# wakeup.net
KiCad netlist of a schematic drawn in EAGLE
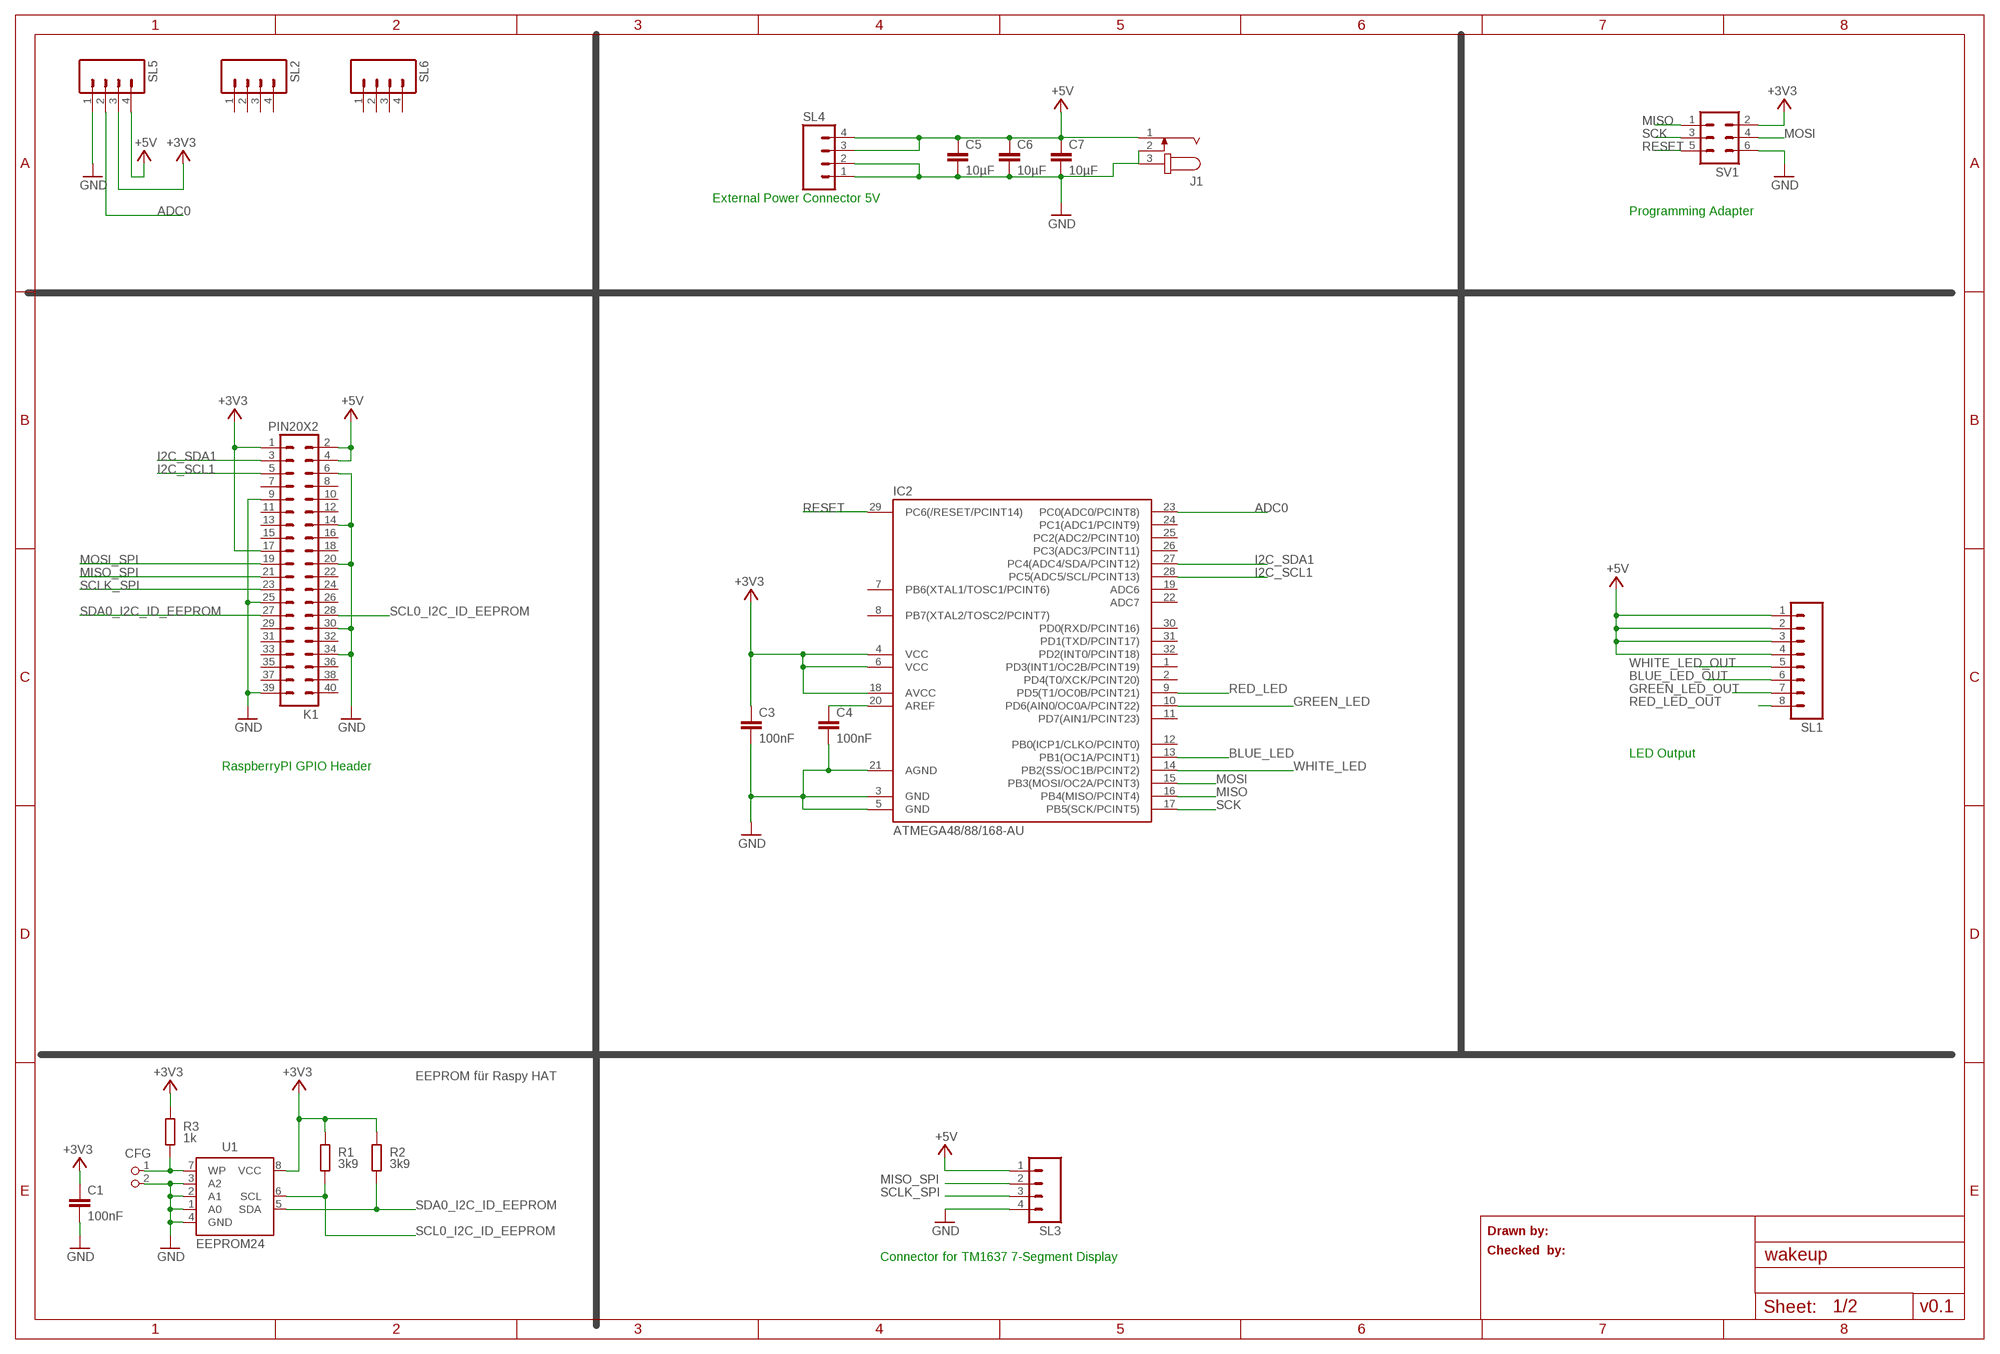
[diagram p0: schematic, sheet 1]
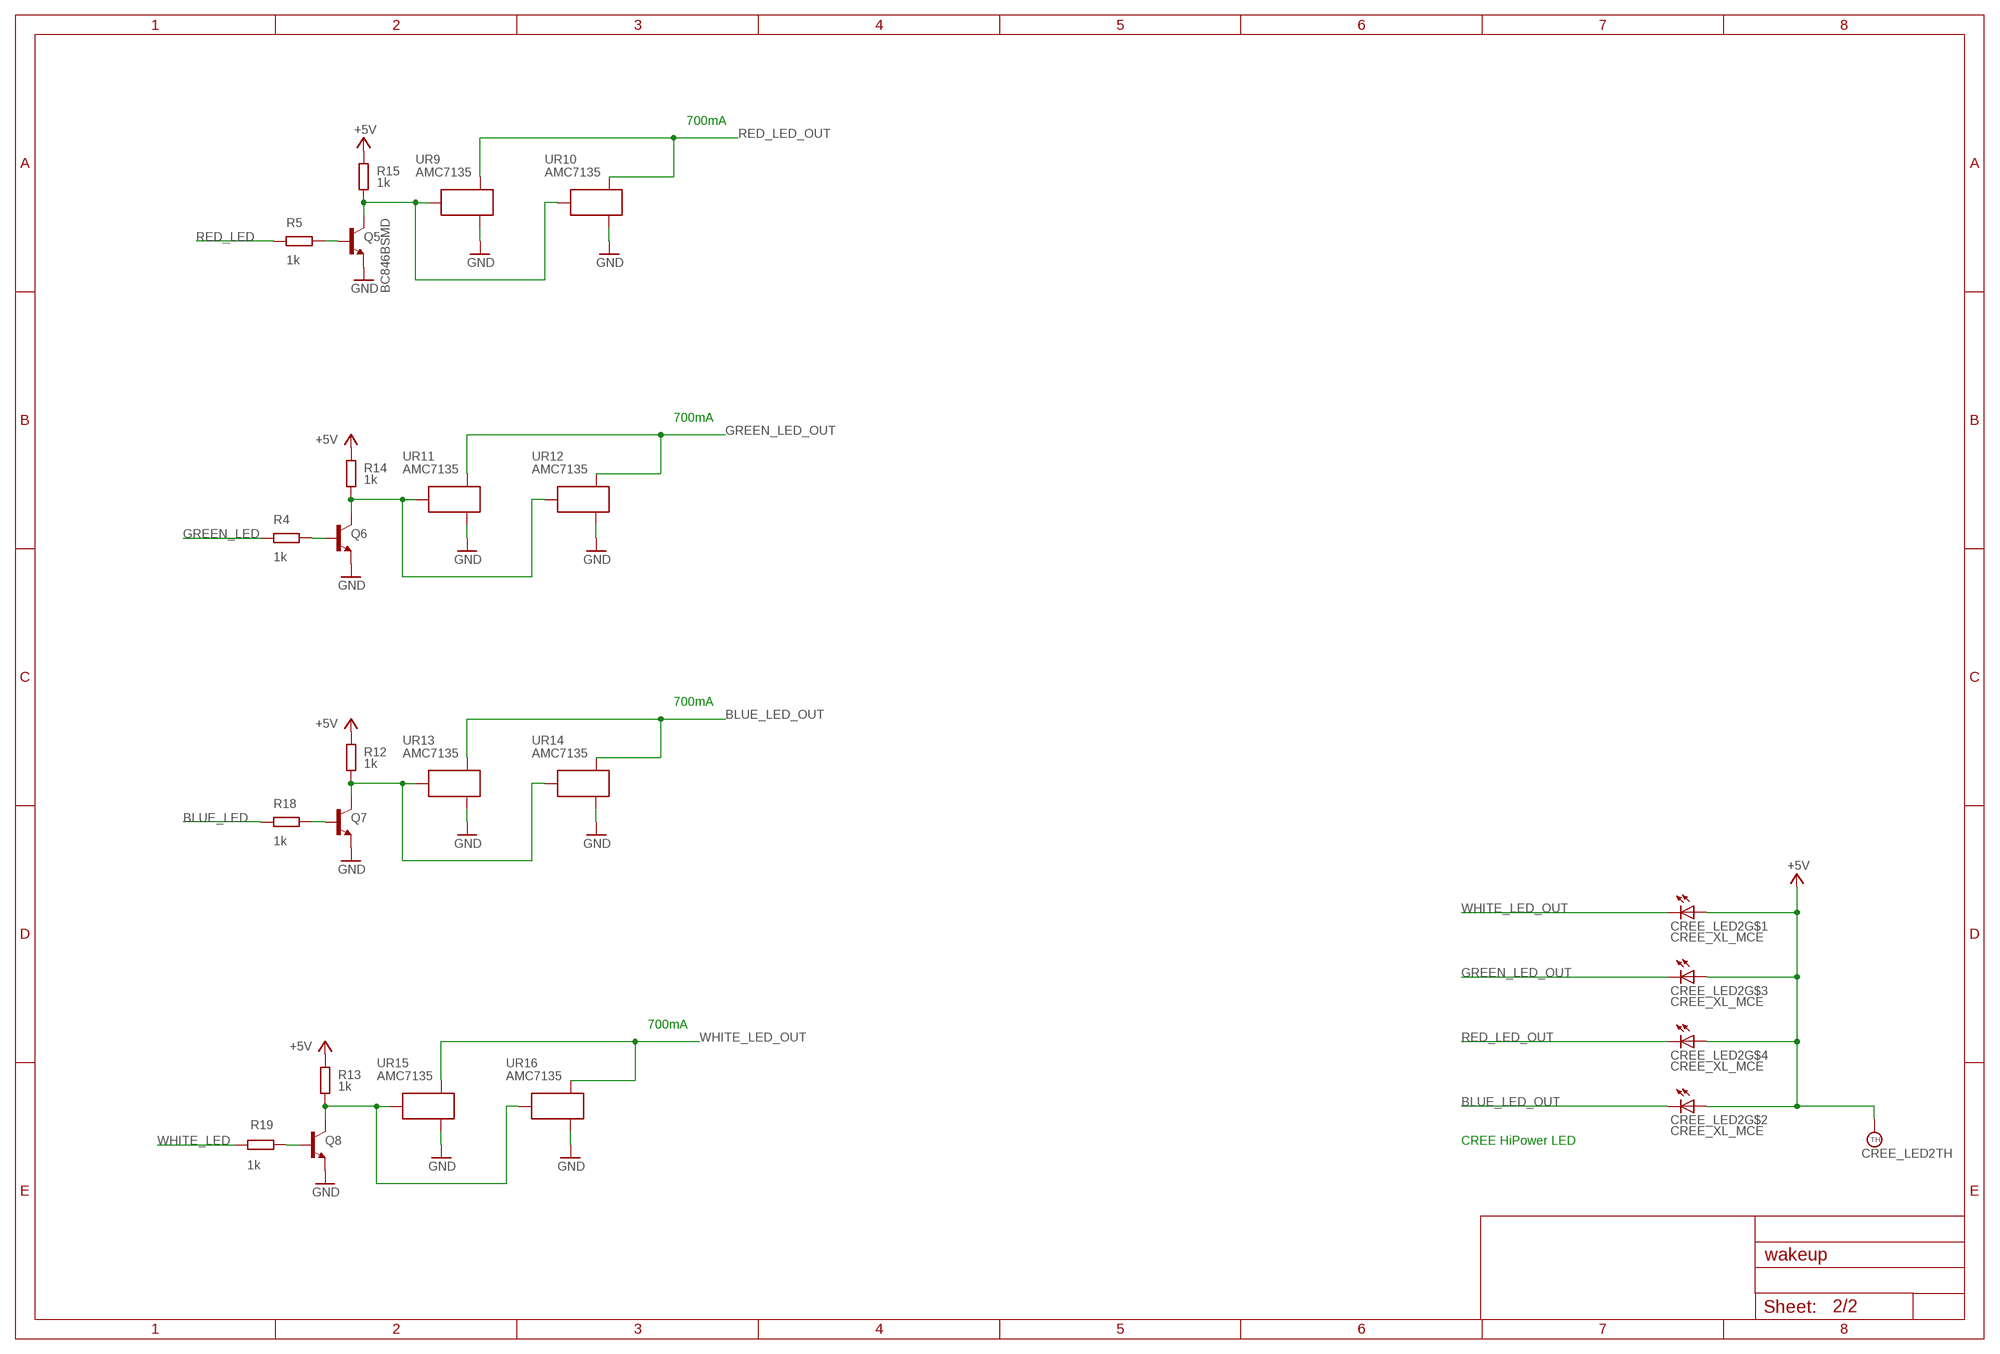
[diagram p1: schematic, sheet 2]

(export (version "E")
  (design (tool "Eeschema 10.0.6"))
  (components
    (comp (ref "C1")
      (value "100nF")
      (footprint "eagle-import:C0805K")
      (libsource (lib "eagle-import") (part "resistor_C-EUC0805K"))
    )
    (comp (ref "C3")
      (value "100nF")
      (footprint "eagle-import:C0603")
      (libsource (lib "eagle-import") (part "C-EUC0603"))
    )
    (comp (ref "C4")
      (value "100nF")
      (footprint "eagle-import:C0603")
      (libsource (lib "eagle-import") (part "C-EUC0603"))
    )
    (comp (ref "C5")
      (value "10µF")
      (footprint "eagle-import:C0805")
      (libsource (lib "eagle-import") (part "C-EUC0805"))
    )
    (comp (ref "C6")
      (value "10µF")
      (footprint "eagle-import:C0805")
      (libsource (lib "eagle-import") (part "C-EUC0805"))
    )
    (comp (ref "C7")
      (value "10µF")
      (footprint "eagle-import:C0805")
      (libsource (lib "eagle-import") (part "C-EUC0805"))
    )
    (comp (ref "CFG")
      (value "PIN2_100")
      (footprint "eagle-import:PIN_W_2")
      (libsource (lib "eagle-import") (part "PIN2_100"))
    )
    (comp (ref "IC2")
      (value "ATMEGA48/88/168-AU")
      (footprint "eagle-import:TQFP32-08")
      (libsource (lib "eagle-import") (part "ATMEGA48/88/168-AU"))
    )
    (comp (ref "J1")
      (value "JACK-PLUG1")
      (footprint "eagle-import:SPC4078")
      (libsource (lib "eagle-import") (part "JACK-PLUG1"))
    )
    (comp (ref "K1")
      (value "PIN20X2")
      (footprint "eagle-import:PIN_20X2")
      (libsource (lib "eagle-import") (part "PIN20X2"))
    )
    (comp (ref "R1")
      (value "3k9")
      (footprint "eagle-import:M0805")
      (fields (field (name "TOLERANCE") "5%"))
      (libsource (lib "eagle-import") (part "R-EU_M0805"))
    )
    (comp (ref "R2")
      (value "3k9")
      (footprint "eagle-import:M0805")
      (fields (field (name "TOLERANCE") "5%"))
      (libsource (lib "eagle-import") (part "R-EU_M0805"))
    )
    (comp (ref "R3")
      (value "1k")
      (footprint "eagle-import:M0805")
      (fields (field (name "TOLERANCE") "5%"))
      (libsource (lib "eagle-import") (part "R-EU_M0805"))
    )
    (comp (ref "SL1")
      (value "M08")
      (footprint "eagle-import:08P")
      (libsource (lib "eagle-import") (part "M08"))
    )
    (comp (ref "SL2")
      (value "M04")
      (footprint "eagle-import:04P")
      (libsource (lib "eagle-import") (part "M04"))
    )
    (comp (ref "SL3")
      (value "M04")
      (footprint "eagle-import:04P")
      (libsource (lib "eagle-import") (part "M04"))
    )
    (comp (ref "SL4")
      (value "M04")
      (footprint "eagle-import:04P")
      (libsource (lib "eagle-import") (part "M04"))
    )
    (comp (ref "SL5")
      (value "M04")
      (footprint "eagle-import:04P")
      (libsource (lib "eagle-import") (part "M04"))
    )
    (comp (ref "SL6")
      (value "M04")
      (footprint "eagle-import:04P")
      (libsource (lib "eagle-import") (part "M04"))
    )
    (comp (ref "SV1")
      (value "ML6")
      (footprint "eagle-import:ML6")
      (libsource (lib "eagle-import") (part "ML6"))
    )
    (comp (ref "U1")
      (value "EEPROM24")
      (footprint "eagle-import:SOIC8")
      (libsource (lib "eagle-import") (part "EEPROM24"))
    )
    (comp (ref "CREE_LED2")
      (value "CREE_XL_MCE")
      (footprint "eagle-import:CREE_XL_MCE")
      (libsource (lib "eagle-import") (part "CREE_XL_MCE"))
    )
    (comp (ref "Q5")
      (value "BC846BSMD")
      (footprint "eagle-import:SOT23")
      (libsource (lib "eagle-import") (part "BC846SMDB"))
    )
    (comp (ref "Q6")
      (value "BC846BSMD")
      (footprint "eagle-import:SOT23")
      (libsource (lib "eagle-import") (part "BC846SMDB"))
    )
    (comp (ref "Q7")
      (value "BC846BSMD")
      (footprint "eagle-import:SOT23")
      (libsource (lib "eagle-import") (part "BC846SMDB"))
    )
    (comp (ref "Q8")
      (value "BC846BSMD")
      (footprint "eagle-import:SOT23")
      (libsource (lib "eagle-import") (part "BC846SMDB"))
    )
    (comp (ref "R4")
      (value "1k")
      (footprint "eagle-import:M0805")
      (fields (field (name "TOLERANCE") "5%"))
      (libsource (lib "eagle-import") (part "R-EU_M0805"))
    )
    (comp (ref "R5")
      (value "1k")
      (footprint "eagle-import:M0805")
      (fields (field (name "TOLERANCE") "5%"))
      (libsource (lib "eagle-import") (part "R-EU_M0805"))
    )
    (comp (ref "R12")
      (value "1k")
      (footprint "eagle-import:R0603")
      (fields (field (name "TOLERANCE") "5%"))
      (libsource (lib "eagle-import") (part "R-EU_R0603"))
    )
    (comp (ref "R13")
      (value "1k")
      (footprint "eagle-import:R0603")
      (fields (field (name "TOLERANCE") "5%"))
      (libsource (lib "eagle-import") (part "R-EU_R0603"))
    )
    (comp (ref "R14")
      (value "1k")
      (footprint "eagle-import:R0603")
      (fields (field (name "TOLERANCE") "5%"))
      (libsource (lib "eagle-import") (part "R-EU_R0603"))
    )
    (comp (ref "R15")
      (value "1k")
      (footprint "eagle-import:R0603")
      (fields (field (name "TOLERANCE") "5%"))
      (libsource (lib "eagle-import") (part "R-EU_R0603"))
    )
    (comp (ref "R18")
      (value "1k")
      (footprint "eagle-import:M0805")
      (fields (field (name "TOLERANCE") "5%"))
      (libsource (lib "eagle-import") (part "R-EU_M0805"))
    )
    (comp (ref "R19")
      (value "1k")
      (footprint "eagle-import:M0805")
      (fields (field (name "TOLERANCE") "5%"))
      (libsource (lib "eagle-import") (part "R-EU_M0805"))
    )
    (comp (ref "UR9")
      (value "AMC7135")
      (footprint "eagle-import:SOT")
      (libsource (lib "eagle-import") (part "AMC7135"))
    )
    (comp (ref "UR10")
      (value "AMC7135")
      (footprint "eagle-import:SOT")
      (libsource (lib "eagle-import") (part "AMC7135"))
    )
    (comp (ref "UR11")
      (value "AMC7135")
      (footprint "eagle-import:SOT")
      (libsource (lib "eagle-import") (part "AMC7135"))
    )
    (comp (ref "UR12")
      (value "AMC7135")
      (footprint "eagle-import:SOT")
      (libsource (lib "eagle-import") (part "AMC7135"))
    )
    (comp (ref "UR13")
      (value "AMC7135")
      (footprint "eagle-import:SOT")
      (libsource (lib "eagle-import") (part "AMC7135"))
    )
    (comp (ref "UR14")
      (value "AMC7135")
      (footprint "eagle-import:SOT")
      (libsource (lib "eagle-import") (part "AMC7135"))
    )
    (comp (ref "UR15")
      (value "AMC7135")
      (footprint "eagle-import:SOT")
      (libsource (lib "eagle-import") (part "AMC7135"))
    )
    (comp (ref "UR16")
      (value "AMC7135")
      (footprint "eagle-import:SOT")
      (libsource (lib "eagle-import") (part "AMC7135"))
    )
  )
  (nets
    (net (code "1") (name "+3V3") (class "Default")
      (node (ref "C1") (pin "1") (pinfunction "1_1") (pintype "passive"))
      (node (ref "C3") (pin "1") (pinfunction "1_1") (pintype "passive"))
      (node (ref "IC2") (pin "18") (pinfunction "AVCC_18") (pintype "passive"))
      (node (ref "IC2") (pin "4") (pinfunction "VCC_4") (pintype "power_in"))
      (node (ref "IC2") (pin "6") (pinfunction "VCC_6") (pintype "power_in"))
      (node (ref "K1") (pin "1") (pinfunction "1_1") (pintype "passive"))
      (node (ref "K1") (pin "17") (pinfunction "17_17") (pintype "passive"))
      (node (ref "R1") (pin "2") (pinfunction "2_2") (pintype "passive"))
      (node (ref "R2") (pin "2") (pinfunction "2_2") (pintype "passive"))
      (node (ref "R3") (pin "2") (pinfunction "2_2") (pintype "passive"))
      (node (ref "SL5") (pin "3") (pinfunction "3_3") (pintype "passive"))
      (node (ref "SV1") (pin "2") (pinfunction "2_2") (pintype "passive"))
      (node (ref "U1") (pin "8") (pinfunction "VCC_8") (pintype "power_in"))
    )
    (net (code "2") (name "+5V") (class "Default")
      (node (ref "C5") (pin "1") (pinfunction "1_1") (pintype "passive"))
      (node (ref "C6") (pin "1") (pinfunction "1_1") (pintype "passive"))
      (node (ref "C7") (pin "1") (pinfunction "1_1") (pintype "passive"))
      (node (ref "CREE_LED2") (pin "1") (pinfunction "A_1") (pintype "passive"))
      (node (ref "CREE_LED2") (pin "2") (pinfunction "A_2") (pintype "passive"))
      (node (ref "CREE_LED2") (pin "3") (pinfunction "A_3") (pintype "passive"))
      (node (ref "CREE_LED2") (pin "4") (pinfunction "A_4") (pintype "passive"))
      (node (ref "CREE_LED2") (pin "HT") (pinfunction "TH_HT") (pintype "passive"))
      (node (ref "J1") (pin "1") (pinfunction "1_1") (pintype "passive"))
      (node (ref "K1") (pin "2") (pinfunction "2_2") (pintype "passive"))
      (node (ref "K1") (pin "4") (pinfunction "4_4") (pintype "passive"))
      (node (ref "R12") (pin "2") (pinfunction "2_2") (pintype "passive"))
      (node (ref "R13") (pin "2") (pinfunction "2_2") (pintype "passive"))
      (node (ref "R14") (pin "2") (pinfunction "2_2") (pintype "passive"))
      (node (ref "R15") (pin "2") (pinfunction "2_2") (pintype "passive"))
      (node (ref "SL1") (pin "1") (pinfunction "1_1") (pintype "passive"))
      (node (ref "SL1") (pin "2") (pinfunction "2_2") (pintype "passive"))
      (node (ref "SL1") (pin "3") (pinfunction "3_3") (pintype "passive"))
      (node (ref "SL1") (pin "4") (pinfunction "4_4") (pintype "passive"))
      (node (ref "SL3") (pin "1") (pinfunction "1_1") (pintype "passive"))
      (node (ref "SL4") (pin "3") (pinfunction "3_3") (pintype "passive"))
      (node (ref "SL4") (pin "4") (pinfunction "4_4") (pintype "passive"))
      (node (ref "SL5") (pin "4") (pinfunction "4_4") (pintype "passive"))
    )
    (net (code "3") (name "ADC0") (class "Default")
      (node (ref "IC2") (pin "23") (pinfunction "PC0(ADC0/PCINT8)_23") (pintype "bidirectional"))
      (node (ref "SL5") (pin "2") (pinfunction "2_2") (pintype "passive"))
    )
    (net (code "4") (name "BLUE_LED") (class "Default")
      (node (ref "IC2") (pin "13") (pinfunction "PB1(OC1A/PCINT1)_13") (pintype "bidirectional"))
      (node (ref "R18") (pin "2") (pinfunction "2_2") (pintype "passive"))
    )
    (net (code "5") (name "BLUE_LED_OUT") (class "Default")
      (node (ref "CREE_LED2") (pin "7") (pinfunction "C_7") (pintype "passive"))
      (node (ref "SL1") (pin "6") (pinfunction "6_6") (pintype "passive"))
      (node (ref "UR13") (pin "1") (pinfunction "OUT_1") (pintype "passive"))
      (node (ref "UR14") (pin "1") (pinfunction "OUT_1") (pintype "passive"))
    )
    (net (code "6") (name "GND") (class "Default")
      (node (ref "C1") (pin "2") (pinfunction "2_2") (pintype "passive"))
      (node (ref "C3") (pin "2") (pinfunction "2_2") (pintype "passive"))
      (node (ref "C4") (pin "2") (pinfunction "2_2") (pintype "passive"))
      (node (ref "C5") (pin "2") (pinfunction "2_2") (pintype "passive"))
      (node (ref "C6") (pin "2") (pinfunction "2_2") (pintype "passive"))
      (node (ref "C7") (pin "2") (pinfunction "2_2") (pintype "passive"))
      (node (ref "CFG") (pin "2") (pinfunction "2_2") (pintype "passive"))
      (node (ref "IC2") (pin "21") (pinfunction "AGND_21") (pintype "power_in"))
      (node (ref "IC2") (pin "3") (pinfunction "GND_3") (pintype "power_in"))
      (node (ref "IC2") (pin "5") (pinfunction "GND_5") (pintype "power_in"))
      (node (ref "J1") (pin "2") (pinfunction "2_2") (pintype "passive"))
      (node (ref "J1") (pin "3") (pinfunction "3_3") (pintype "passive"))
      (node (ref "K1") (pin "14") (pinfunction "14_14") (pintype "passive"))
      (node (ref "K1") (pin "20") (pinfunction "20_20") (pintype "passive"))
      (node (ref "K1") (pin "25") (pinfunction "25_25") (pintype "passive"))
      (node (ref "K1") (pin "30") (pinfunction "30_30") (pintype "passive"))
      (node (ref "K1") (pin "34") (pinfunction "34_34") (pintype "passive"))
      (node (ref "K1") (pin "39") (pinfunction "39_39") (pintype "passive"))
      (node (ref "K1") (pin "6") (pinfunction "6_6") (pintype "passive"))
      (node (ref "K1") (pin "9") (pinfunction "9_9") (pintype "passive"))
      (node (ref "Q5") (pin "2") (pinfunction "E_2") (pintype "passive"))
      (node (ref "Q6") (pin "2") (pinfunction "E_2") (pintype "passive"))
      (node (ref "Q7") (pin "2") (pinfunction "E_2") (pintype "passive"))
      (node (ref "Q8") (pin "2") (pinfunction "E_2") (pintype "passive"))
      (node (ref "SL3") (pin "4") (pinfunction "4_4") (pintype "passive"))
      (node (ref "SL4") (pin "1") (pinfunction "1_1") (pintype "passive"))
      (node (ref "SL4") (pin "2") (pinfunction "2_2") (pintype "passive"))
      (node (ref "SL5") (pin "1") (pinfunction "1_1") (pintype "passive"))
      (node (ref "SV1") (pin "6") (pinfunction "6_6") (pintype "passive"))
      (node (ref "U1") (pin "1") (pinfunction "A0_1") (pintype "input"))
      (node (ref "U1") (pin "2") (pinfunction "A1_2") (pintype "input"))
      (node (ref "U1") (pin "3") (pinfunction "A2_3") (pintype "input"))
      (node (ref "U1") (pin "4") (pinfunction "GND_4") (pintype "power_in"))
      (node (ref "UR10") (pin "2") (pinfunction "GND_2") (pintype "passive"))
      (node (ref "UR10") (pin "2@1") (pinfunction "GND_2@1") (pintype "passive"))
      (node (ref "UR11") (pin "2") (pinfunction "GND_2") (pintype "passive"))
      (node (ref "UR11") (pin "2@1") (pinfunction "GND_2@1") (pintype "passive"))
      (node (ref "UR12") (pin "2") (pinfunction "GND_2") (pintype "passive"))
      (node (ref "UR12") (pin "2@1") (pinfunction "GND_2@1") (pintype "passive"))
      (node (ref "UR13") (pin "2") (pinfunction "GND_2") (pintype "passive"))
      (node (ref "UR13") (pin "2@1") (pinfunction "GND_2@1") (pintype "passive"))
      (node (ref "UR14") (pin "2") (pinfunction "GND_2") (pintype "passive"))
      (node (ref "UR14") (pin "2@1") (pinfunction "GND_2@1") (pintype "passive"))
      (node (ref "UR15") (pin "2") (pinfunction "GND_2") (pintype "passive"))
      (node (ref "UR15") (pin "2@1") (pinfunction "GND_2@1") (pintype "passive"))
      (node (ref "UR16") (pin "2") (pinfunction "GND_2") (pintype "passive"))
      (node (ref "UR16") (pin "2@1") (pinfunction "GND_2@1") (pintype "passive"))
      (node (ref "UR9") (pin "2") (pinfunction "GND_2") (pintype "passive"))
      (node (ref "UR9") (pin "2@1") (pinfunction "GND_2@1") (pintype "passive"))
    )
    (net (code "7") (name "GREEN_LED") (class "Default")
      (node (ref "IC2") (pin "10") (pinfunction "PD6(AIN0/OC0A/PCINT22)_10") (pintype "bidirectional"))
      (node (ref "R4") (pin "2") (pinfunction "2_2") (pintype "passive"))
    )
    (net (code "8") (name "GREEN_LED_OUT") (class "Default")
      (node (ref "CREE_LED2") (pin "6") (pinfunction "C_6") (pintype "passive"))
      (node (ref "SL1") (pin "7") (pinfunction "7_7") (pintype "passive"))
      (node (ref "UR11") (pin "1") (pinfunction "OUT_1") (pintype "passive"))
      (node (ref "UR12") (pin "1") (pinfunction "OUT_1") (pintype "passive"))
    )
    (net (code "9") (name "I2C_SCL1") (class "Default")
      (node (ref "IC2") (pin "28") (pinfunction "PC5(ADC5/SCL/PCINT13)_28") (pintype "bidirectional"))
      (node (ref "K1") (pin "5") (pinfunction "5_5") (pintype "passive"))
    )
    (net (code "10") (name "I2C_SDA1") (class "Default")
      (node (ref "IC2") (pin "27") (pinfunction "PC4(ADC4/SDA/PCINT12)_27") (pintype "bidirectional"))
      (node (ref "K1") (pin "3") (pinfunction "3_3") (pintype "passive"))
    )
    (net (code "11") (name "MISO") (class "Default")
      (node (ref "IC2") (pin "16") (pinfunction "PB4(MISO/PCINT4)_16") (pintype "bidirectional"))
      (node (ref "SV1") (pin "1") (pinfunction "1_1") (pintype "passive"))
    )
    (net (code "12") (name "MISO_SPI") (class "Default")
      (node (ref "K1") (pin "21") (pinfunction "21_21") (pintype "passive"))
      (node (ref "SL3") (pin "2") (pinfunction "2_2") (pintype "passive"))
    )
    (net (code "13") (name "MOSI") (class "Default")
      (node (ref "IC2") (pin "15") (pinfunction "PB3(MOSI/OC2A/PCINT3)_15") (pintype "bidirectional"))
      (node (ref "SV1") (pin "4") (pinfunction "4_4") (pintype "passive"))
    )
    (net (code "14") (name "MOSI_SPI") (class "Default")
      (node (ref "K1") (pin "19") (pinfunction "19_19") (pintype "passive"))
    )
    (net (code "15") (name "Net-(IC2-AREF)") (class "Default")
      (node (ref "C4") (pin "1") (pinfunction "1_1") (pintype "passive"))
      (node (ref "IC2") (pin "20") (pinfunction "AREF_20") (pintype "passive"))
    )
    (net (code "16") (name "Net-(Q5-B)") (class "Default")
      (node (ref "Q5") (pin "1") (pinfunction "B_1") (pintype "passive"))
      (node (ref "R5") (pin "1") (pinfunction "1_1") (pintype "passive"))
    )
    (net (code "17") (name "Net-(Q5-C)") (class "Default")
      (node (ref "Q5") (pin "3") (pinfunction "C_3") (pintype "passive"))
      (node (ref "R15") (pin "1") (pinfunction "1_1") (pintype "passive"))
      (node (ref "UR10") (pin "3") (pinfunction "VDD_3") (pintype "passive"))
      (node (ref "UR9") (pin "3") (pinfunction "VDD_3") (pintype "passive"))
    )
    (net (code "18") (name "Net-(Q6-B)") (class "Default")
      (node (ref "Q6") (pin "1") (pinfunction "B_1") (pintype "passive"))
      (node (ref "R4") (pin "1") (pinfunction "1_1") (pintype "passive"))
    )
    (net (code "19") (name "Net-(Q6-C)") (class "Default")
      (node (ref "Q6") (pin "3") (pinfunction "C_3") (pintype "passive"))
      (node (ref "R14") (pin "1") (pinfunction "1_1") (pintype "passive"))
      (node (ref "UR11") (pin "3") (pinfunction "VDD_3") (pintype "passive"))
      (node (ref "UR12") (pin "3") (pinfunction "VDD_3") (pintype "passive"))
    )
    (net (code "20") (name "Net-(Q7-B)") (class "Default")
      (node (ref "Q7") (pin "1") (pinfunction "B_1") (pintype "passive"))
      (node (ref "R18") (pin "1") (pinfunction "1_1") (pintype "passive"))
    )
    (net (code "21") (name "Net-(Q7-C)") (class "Default")
      (node (ref "Q7") (pin "3") (pinfunction "C_3") (pintype "passive"))
      (node (ref "R12") (pin "1") (pinfunction "1_1") (pintype "passive"))
      (node (ref "UR13") (pin "3") (pinfunction "VDD_3") (pintype "passive"))
      (node (ref "UR14") (pin "3") (pinfunction "VDD_3") (pintype "passive"))
    )
    (net (code "22") (name "Net-(Q8-B)") (class "Default")
      (node (ref "Q8") (pin "1") (pinfunction "B_1") (pintype "passive"))
      (node (ref "R19") (pin "1") (pinfunction "1_1") (pintype "passive"))
    )
    (net (code "23") (name "Net-(Q8-C)") (class "Default")
      (node (ref "Q8") (pin "3") (pinfunction "C_3") (pintype "passive"))
      (node (ref "R13") (pin "1") (pinfunction "1_1") (pintype "passive"))
      (node (ref "UR15") (pin "3") (pinfunction "VDD_3") (pintype "passive"))
      (node (ref "UR16") (pin "3") (pinfunction "VDD_3") (pintype "passive"))
    )
    (net (code "24") (name "Net-(U1-WP)") (class "Default")
      (node (ref "CFG") (pin "1") (pinfunction "1_1") (pintype "passive"))
      (node (ref "R3") (pin "1") (pinfunction "1_1") (pintype "passive"))
      (node (ref "U1") (pin "7") (pinfunction "WP_7") (pintype "input"))
    )
    (net (code "25") (name "RED_LED") (class "Default")
      (node (ref "IC2") (pin "9") (pinfunction "PD5(T1/OC0B/PCINT21)_9") (pintype "bidirectional"))
      (node (ref "R5") (pin "2") (pinfunction "2_2") (pintype "passive"))
    )
    (net (code "26") (name "RED_LED_OUT") (class "Default")
      (node (ref "CREE_LED2") (pin "5") (pinfunction "C_5") (pintype "passive"))
      (node (ref "SL1") (pin "8") (pinfunction "8_8") (pintype "passive"))
      (node (ref "UR10") (pin "1") (pinfunction "OUT_1") (pintype "passive"))
      (node (ref "UR9") (pin "1") (pinfunction "OUT_1") (pintype "passive"))
    )
    (net (code "27") (name "RESET") (class "Default")
      (node (ref "IC2") (pin "29") (pinfunction "PC6(/RESET/PCINT14)_29") (pintype "bidirectional"))
      (node (ref "SV1") (pin "5") (pinfunction "5_5") (pintype "passive"))
    )
    (net (code "28") (name "SCK") (class "Default")
      (node (ref "IC2") (pin "17") (pinfunction "PB5(SCK/PCINT5)_17") (pintype "bidirectional"))
      (node (ref "SV1") (pin "3") (pinfunction "3_3") (pintype "passive"))
    )
    (net (code "29") (name "SCL0_I2C_ID_EEPROM") (class "Default")
      (node (ref "K1") (pin "28") (pinfunction "28_28") (pintype "passive"))
      (node (ref "R1") (pin "1") (pinfunction "1_1") (pintype "passive"))
      (node (ref "U1") (pin "6") (pinfunction "SCL_6") (pintype "input"))
    )
    (net (code "30") (name "SCLK_SPI") (class "Default")
      (node (ref "K1") (pin "23") (pinfunction "23_23") (pintype "passive"))
      (node (ref "SL3") (pin "3") (pinfunction "3_3") (pintype "passive"))
    )
    (net (code "31") (name "SDA0_I2C_ID_EEPROM") (class "Default")
      (node (ref "K1") (pin "27") (pinfunction "27_27") (pintype "passive"))
      (node (ref "R2") (pin "1") (pinfunction "1_1") (pintype "passive"))
      (node (ref "U1") (pin "5") (pinfunction "SDA_5") (pintype "bidirectional"))
    )
    (net (code "32") (name "WHITE_LED") (class "Default")
      (node (ref "IC2") (pin "14") (pinfunction "PB2(SS/OC1B/PCINT2)_14") (pintype "bidirectional"))
      (node (ref "R19") (pin "2") (pinfunction "2_2") (pintype "passive"))
    )
    (net (code "33") (name "WHITE_LED_OUT") (class "Default")
      (node (ref "CREE_LED2") (pin "8") (pinfunction "C_8") (pintype "passive"))
      (node (ref "SL1") (pin "5") (pinfunction "5_5") (pintype "passive"))
      (node (ref "UR15") (pin "1") (pinfunction "OUT_1") (pintype "passive"))
      (node (ref "UR16") (pin "1") (pinfunction "OUT_1") (pintype "passive"))
    )
    (net (code "34") (name "unconnected-(IC2-ADC6-Pad19)") (class "Default")
      (node (ref "IC2") (pin "19") (pinfunction "ADC6_19") (pintype "passive"))
    )
    (net (code "35") (name "unconnected-(IC2-ADC7-Pad22)") (class "Default")
      (node (ref "IC2") (pin "22") (pinfunction "ADC7_22") (pintype "passive"))
    )
    (net (code "36") (name "unconnected-(IC2-PB0(ICP1{slash}CLKO{slash}PCINT0)-Pad12)") (class "Default")
      (node (ref "IC2") (pin "12") (pinfunction "PB0(ICP1/CLKO/PCINT0)_12") (pintype "bidirectional"))
    )
    (net (code "37") (name "unconnected-(IC2-PB6(XTAL1{slash}TOSC1{slash}PCINT6)-Pad7)") (class "Default")
      (node (ref "IC2") (pin "7") (pinfunction "PB6(XTAL1/TOSC1/PCINT6)_7") (pintype "bidirectional"))
    )
    (net (code "38") (name "unconnected-(IC2-PB7(XTAL2{slash}TOSC2{slash}PCINT7)-Pad8)") (class "Default")
      (node (ref "IC2") (pin "8") (pinfunction "PB7(XTAL2/TOSC2/PCINT7)_8") (pintype "bidirectional"))
    )
    (net (code "39") (name "unconnected-(IC2-PC1(ADC1{slash}PCINT9)-Pad24)") (class "Default")
      (node (ref "IC2") (pin "24") (pinfunction "PC1(ADC1/PCINT9)_24") (pintype "bidirectional"))
    )
    (net (code "40") (name "unconnected-(IC2-PC2(ADC2{slash}PCINT10)-Pad25)") (class "Default")
      (node (ref "IC2") (pin "25") (pinfunction "PC2(ADC2/PCINT10)_25") (pintype "bidirectional"))
    )
    (net (code "41") (name "unconnected-(IC2-PC3(ADC3{slash}PCINT11)-Pad26)") (class "Default")
      (node (ref "IC2") (pin "26") (pinfunction "PC3(ADC3/PCINT11)_26") (pintype "bidirectional"))
    )
    (net (code "42") (name "unconnected-(IC2-PD0(RXD{slash}PCINT16)-Pad30)") (class "Default")
      (node (ref "IC2") (pin "30") (pinfunction "PD0(RXD/PCINT16)_30") (pintype "bidirectional"))
    )
    (net (code "43") (name "unconnected-(IC2-PD1(TXD{slash}PCINT17)-Pad31)") (class "Default")
      (node (ref "IC2") (pin "31") (pinfunction "PD1(TXD/PCINT17)_31") (pintype "bidirectional"))
    )
    (net (code "44") (name "unconnected-(IC2-PD2(INT0{slash}PCINT18)-Pad32)") (class "Default")
      (node (ref "IC2") (pin "32") (pinfunction "PD2(INT0/PCINT18)_32") (pintype "bidirectional"))
    )
    (net (code "45") (name "unconnected-(IC2-PD3(INT1{slash}OC2B{slash}PCINT19)-Pad1)") (class "Default")
      (node (ref "IC2") (pin "1") (pinfunction "PD3(INT1/OC2B/PCINT19)_1") (pintype "bidirectional"))
    )
    (net (code "46") (name "unconnected-(IC2-PD4(T0{slash}XCK{slash}PCINT20)-Pad2)") (class "Default")
      (node (ref "IC2") (pin "2") (pinfunction "PD4(T0/XCK/PCINT20)_2") (pintype "bidirectional"))
    )
    (net (code "47") (name "unconnected-(IC2-PD7(AIN1{slash}PCINT23)-Pad11)") (class "Default")
      (node (ref "IC2") (pin "11") (pinfunction "PD7(AIN1/PCINT23)_11") (pintype "bidirectional"))
    )
    (net (code "48") (name "unconnected-(K1-Pad7)") (class "Default")
      (node (ref "K1") (pin "7") (pinfunction "7_7") (pintype "passive"))
    )
    (net (code "49") (name "unconnected-(K1-Pad8)") (class "Default")
      (node (ref "K1") (pin "8") (pinfunction "8_8") (pintype "passive"))
    )
    (net (code "50") (name "unconnected-(K1-Pad10)") (class "Default")
      (node (ref "K1") (pin "10") (pinfunction "10_10") (pintype "passive"))
    )
    (net (code "51") (name "unconnected-(K1-Pad11)") (class "Default")
      (node (ref "K1") (pin "11") (pinfunction "11_11") (pintype "passive"))
    )
    (net (code "52") (name "unconnected-(K1-Pad12)") (class "Default")
      (node (ref "K1") (pin "12") (pinfunction "12_12") (pintype "passive"))
    )
    (net (code "53") (name "unconnected-(K1-Pad13)") (class "Default")
      (node (ref "K1") (pin "13") (pinfunction "13_13") (pintype "passive"))
    )
    (net (code "54") (name "unconnected-(K1-Pad15)") (class "Default")
      (node (ref "K1") (pin "15") (pinfunction "15_15") (pintype "passive"))
    )
    (net (code "55") (name "unconnected-(K1-Pad16)") (class "Default")
      (node (ref "K1") (pin "16") (pinfunction "16_16") (pintype "passive"))
    )
    (net (code "56") (name "unconnected-(K1-Pad18)") (class "Default")
      (node (ref "K1") (pin "18") (pinfunction "18_18") (pintype "passive"))
    )
    (net (code "57") (name "unconnected-(K1-Pad22)") (class "Default")
      (node (ref "K1") (pin "22") (pinfunction "22_22") (pintype "passive"))
    )
    (net (code "58") (name "unconnected-(K1-Pad24)") (class "Default")
      (node (ref "K1") (pin "24") (pinfunction "24_24") (pintype "passive"))
    )
    (net (code "59") (name "unconnected-(K1-Pad26)") (class "Default")
      (node (ref "K1") (pin "26") (pinfunction "26_26") (pintype "passive"))
    )
    (net (code "60") (name "unconnected-(K1-Pad29)") (class "Default")
      (node (ref "K1") (pin "29") (pinfunction "29_29") (pintype "passive"))
    )
    (net (code "61") (name "unconnected-(K1-Pad31)") (class "Default")
      (node (ref "K1") (pin "31") (pinfunction "31_31") (pintype "passive"))
    )
    (net (code "62") (name "unconnected-(K1-Pad32)") (class "Default")
      (node (ref "K1") (pin "32") (pinfunction "32_32") (pintype "passive"))
    )
    (net (code "63") (name "unconnected-(K1-Pad33)") (class "Default")
      (node (ref "K1") (pin "33") (pinfunction "33_33") (pintype "passive"))
    )
    (net (code "64") (name "unconnected-(K1-Pad35)") (class "Default")
      (node (ref "K1") (pin "35") (pinfunction "35_35") (pintype "passive"))
    )
    (net (code "65") (name "unconnected-(K1-Pad36)") (class "Default")
      (node (ref "K1") (pin "36") (pinfunction "36_36") (pintype "passive"))
    )
    (net (code "66") (name "unconnected-(K1-Pad37)") (class "Default")
      (node (ref "K1") (pin "37") (pinfunction "37_37") (pintype "passive"))
    )
    (net (code "67") (name "unconnected-(K1-Pad38)") (class "Default")
      (node (ref "K1") (pin "38") (pinfunction "38_38") (pintype "passive"))
    )
    (net (code "68") (name "unconnected-(K1-Pad40)") (class "Default")
      (node (ref "K1") (pin "40") (pinfunction "40_40") (pintype "passive"))
    )
    (net (code "69") (name "unconnected-(SL2-Pad1)") (class "Default")
      (node (ref "SL2") (pin "1") (pinfunction "1_1") (pintype "passive"))
    )
    (net (code "70") (name "unconnected-(SL2-Pad2)") (class "Default")
      (node (ref "SL2") (pin "2") (pinfunction "2_2") (pintype "passive"))
    )
    (net (code "71") (name "unconnected-(SL2-Pad3)") (class "Default")
      (node (ref "SL2") (pin "3") (pinfunction "3_3") (pintype "passive"))
    )
    (net (code "72") (name "unconnected-(SL2-Pad4)") (class "Default")
      (node (ref "SL2") (pin "4") (pinfunction "4_4") (pintype "passive"))
    )
    (net (code "73") (name "unconnected-(SL6-Pad1)") (class "Default")
      (node (ref "SL6") (pin "1") (pinfunction "1_1") (pintype "passive"))
    )
    (net (code "74") (name "unconnected-(SL6-Pad2)") (class "Default")
      (node (ref "SL6") (pin "2") (pinfunction "2_2") (pintype "passive"))
    )
    (net (code "75") (name "unconnected-(SL6-Pad3)") (class "Default")
      (node (ref "SL6") (pin "3") (pinfunction "3_3") (pintype "passive"))
    )
    (net (code "76") (name "unconnected-(SL6-Pad4)") (class "Default")
      (node (ref "SL6") (pin "4") (pinfunction "4_4") (pintype "passive"))
    )
  )
)
